# bletka_1.net
KiCad netlist of a schematic drawn in EAGLE
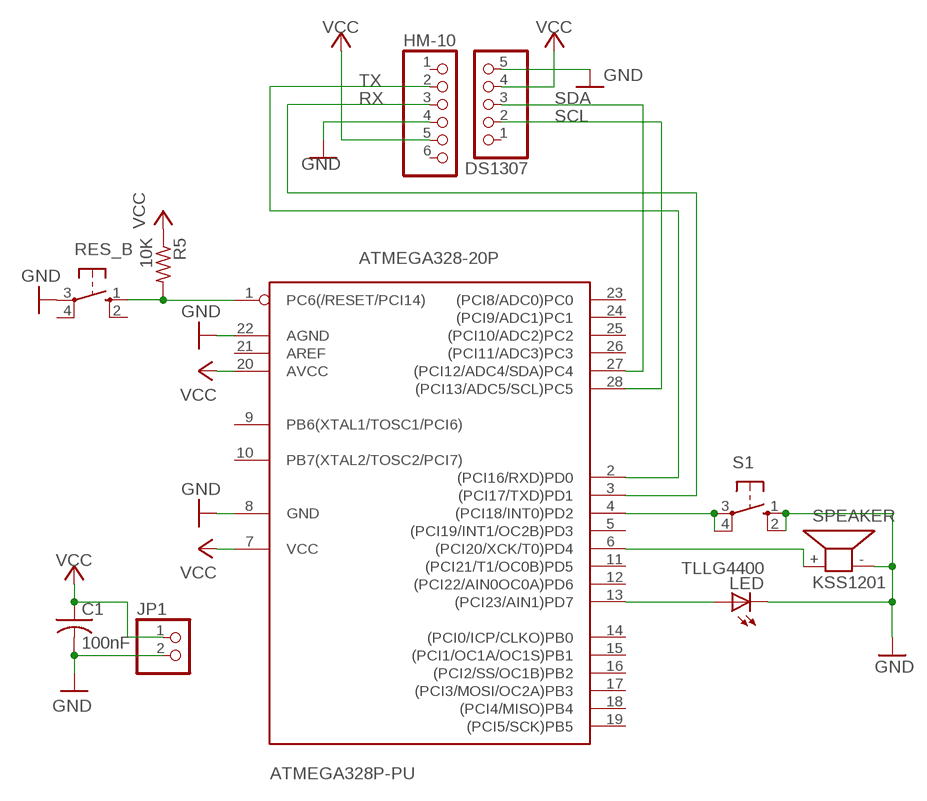
[diagram p0: schematic, sheet 1]

(export (version "E")
  (design (tool "Eeschema 10.0.6"))
  (components
    (comp (ref "ATMEGA328P-PU")
      (value "ATMEGA328-20P")
      (footprint "eagle-import:DIL28-3")
      (libsource (lib "eagle-import") (part "ATMEGA328P-20"))
    )
    (comp (ref "C1")
      (value "100nF")
      (footprint "eagle-import:C050-024X044")
      (libsource (lib "eagle-import") (part "C-US050-024X044"))
    )
    (comp (ref "DS1307")
      (value "PINHD-1X5")
      (footprint "eagle-import:1X05")
      (libsource (lib "eagle-import") (part "PINHD-1X5"))
    )
    (comp (ref "HM-10")
      (value "PINHD-1X6")
      (footprint "eagle-import:1X06")
      (libsource (lib "eagle-import") (part "PINHD-1X6"))
    )
    (comp (ref "JP1")
      (value "PINHD-1X2")
      (footprint "eagle-import:1X02")
      (libsource (lib "eagle-import") (part "PINHD-1X2"))
    )
    (comp (ref "LED")
      (value "TLLG4400")
      (footprint "eagle-import:LED3MM")
      (fields (field (name "MF") "VISHAY SEMICONDUCTOR"))
      (libsource (lib "eagle-import") (part "TLLG4400"))
    )
    (comp (ref "R5")
      (value "10K")
      (footprint "eagle-import:0207_10")
      (libsource (lib "eagle-import") (part "R-US_0207/10"))
    )
    (comp (ref "RES_B")
      (value "10-XX")
      (footprint "eagle-import:B3F-10XX")
      (fields (field (name "MPN") "B3F-1000"))
      (libsource (lib "eagle-import") (part "10-XX"))
    )
    (comp (ref "S1")
      (value "10-XX")
      (footprint "eagle-import:B3F-10XX")
      (fields (field (name "MPN") "B3F-1000"))
      (libsource (lib "eagle-import") (part "10-XX"))
    )
    (comp (ref "SPEAKER")
      (value "KSS1201")
      (footprint "eagle-import:KSS1201")
      (libsource (lib "eagle-import") (part "KSS1201"))
    )
  )
  (nets
    (net (code "1") (name "/RX") (class "Default")
      (node (ref "ATMEGA328P-PU") (pin "3") (pinfunction "(PCI17/TXD)PD1_3") (pintype "bidirectional"))
      (node (ref "HM-10") (pin "3") (pinfunction "3_3") (pintype "passive"))
    )
    (net (code "2") (name "/SCL") (class "Default")
      (node (ref "ATMEGA328P-PU") (pin "28") (pinfunction "(PCI13/ADC5/SCL)PC5_28") (pintype "bidirectional"))
      (node (ref "DS1307") (pin "2") (pinfunction "2_2") (pintype "passive"))
    )
    (net (code "3") (name "/SDA") (class "Default")
      (node (ref "ATMEGA328P-PU") (pin "27") (pinfunction "(PCI12/ADC4/SDA)PC4_27") (pintype "bidirectional"))
      (node (ref "DS1307") (pin "3") (pinfunction "3_3") (pintype "passive"))
    )
    (net (code "4") (name "/TX") (class "Default")
      (node (ref "ATMEGA328P-PU") (pin "2") (pinfunction "(PCI16/RXD)PD0_2") (pintype "bidirectional"))
      (node (ref "HM-10") (pin "2") (pinfunction "2_2") (pintype "passive"))
    )
    (net (code "5") (name "GND") (class "Default")
      (node (ref "ATMEGA328P-PU") (pin "22") (pinfunction "AGND_22") (pintype "bidirectional"))
      (node (ref "ATMEGA328P-PU") (pin "8") (pinfunction "GND_8") (pintype "bidirectional"))
      (node (ref "C1") (pin "2") (pinfunction "2_2") (pintype "passive"))
      (node (ref "DS1307") (pin "5") (pinfunction "5_5") (pintype "passive"))
      (node (ref "HM-10") (pin "4") (pinfunction "4_4") (pintype "passive"))
      (node (ref "JP1") (pin "2") (pinfunction "2_2") (pintype "passive"))
      (node (ref "LED") (pin "K") (pinfunction "C_K") (pintype "passive"))
      (node (ref "RES_B") (pin "3") (pinfunction "P_3") (pintype "passive"))
      (node (ref "S1") (pin "1") (pinfunction "S_1") (pintype "passive"))
      (node (ref "S1") (pin "2") (pinfunction "S1_2") (pintype "passive"))
      (node (ref "SPEAKER") (pin "-") (pinfunction "2_-") (pintype "passive"))
    )
    (net (code "6") (name "Net-(ATMEGA328P-PU-(PCI18{slash}INT0)PD2)") (class "Default")
      (node (ref "ATMEGA328P-PU") (pin "4") (pinfunction "(PCI18/INT0)PD2_4") (pintype "bidirectional"))
      (node (ref "S1") (pin "3") (pinfunction "P_3") (pintype "passive"))
      (node (ref "S1") (pin "4") (pinfunction "P1_4") (pintype "passive"))
    )
    (net (code "7") (name "Net-(ATMEGA328P-PU-(PCI20{slash}XCK{slash}T0)PD4)") (class "Default")
      (node (ref "ATMEGA328P-PU") (pin "6") (pinfunction "(PCI20/XCK/T0)PD4_6") (pintype "bidirectional"))
      (node (ref "SPEAKER") (pin "+") (pinfunction "1_+") (pintype "passive"))
    )
    (net (code "8") (name "Net-(ATMEGA328P-PU-(PCI23{slash}AIN1)PD7)") (class "Default")
      (node (ref "ATMEGA328P-PU") (pin "13") (pinfunction "(PCI23/AIN1)PD7_13") (pintype "bidirectional"))
      (node (ref "LED") (pin "A") (pinfunction "A_A") (pintype "passive"))
    )
    (net (code "9") (name "Net-(ATMEGA328P-PU-PC6({slash}RESET{slash}PCI14))") (class "Default")
      (node (ref "ATMEGA328P-PU") (pin "1") (pinfunction "PC6(/RESET/PCI14)_1") (pintype "bidirectional"))
      (node (ref "R5") (pin "2") (pinfunction "2_2") (pintype "passive"))
      (node (ref "RES_B") (pin "1") (pinfunction "S_1") (pintype "passive"))
    )
    (net (code "10") (name "VCC") (class "Default")
      (node (ref "ATMEGA328P-PU") (pin "20") (pinfunction "AVCC_20") (pintype "bidirectional"))
      (node (ref "ATMEGA328P-PU") (pin "7") (pinfunction "VCC_7") (pintype "bidirectional"))
      (node (ref "C1") (pin "1") (pinfunction "1_1") (pintype "passive"))
      (node (ref "DS1307") (pin "4") (pinfunction "4_4") (pintype "passive"))
      (node (ref "HM-10") (pin "5") (pinfunction "5_5") (pintype "passive"))
      (node (ref "JP1") (pin "1") (pinfunction "1_1") (pintype "passive"))
      (node (ref "R5") (pin "1") (pinfunction "1_1") (pintype "passive"))
    )
    (net (code "11") (name "unconnected-(ATMEGA328P-PU-(PCI0{slash}ICP{slash}CLKO)PB0-Pad14)") (class "Default")
      (node (ref "ATMEGA328P-PU") (pin "14") (pinfunction "(PCI0/ICP/CLKO)PB0_14") (pintype "bidirectional"))
    )
    (net (code "12") (name "unconnected-(ATMEGA328P-PU-(PCI1{slash}OC1A{slash}OC1S)PB1-Pad15)") (class "Default")
      (node (ref "ATMEGA328P-PU") (pin "15") (pinfunction "(PCI1/OC1A/OC1S)PB1_15") (pintype "bidirectional"))
    )
    (net (code "13") (name "unconnected-(ATMEGA328P-PU-(PCI2{slash}SS{slash}OC1B)PB2-Pad16)") (class "Default")
      (node (ref "ATMEGA328P-PU") (pin "16") (pinfunction "(PCI2/SS/OC1B)PB2_16") (pintype "bidirectional"))
    )
    (net (code "14") (name "unconnected-(ATMEGA328P-PU-(PCI3{slash}MOSI{slash}OC2A)PB3-Pad17)") (class "Default")
      (node (ref "ATMEGA328P-PU") (pin "17") (pinfunction "(PCI3/MOSI/OC2A)PB3_17") (pintype "bidirectional"))
    )
    (net (code "15") (name "unconnected-(ATMEGA328P-PU-(PCI4{slash}MISO)PB4-Pad18)") (class "Default")
      (node (ref "ATMEGA328P-PU") (pin "18") (pinfunction "(PCI4/MISO)PB4_18") (pintype "bidirectional"))
    )
    (net (code "16") (name "unconnected-(ATMEGA328P-PU-(PCI5{slash}SCK)PB5-Pad19)") (class "Default")
      (node (ref "ATMEGA328P-PU") (pin "19") (pinfunction "(PCI5/SCK)PB5_19") (pintype "bidirectional"))
    )
    (net (code "17") (name "unconnected-(ATMEGA328P-PU-(PCI8{slash}ADC0)PC0-Pad23)") (class "Default")
      (node (ref "ATMEGA328P-PU") (pin "23") (pinfunction "(PCI8/ADC0)PC0_23") (pintype "bidirectional"))
    )
    (net (code "18") (name "unconnected-(ATMEGA328P-PU-(PCI9{slash}ADC1)PC1-Pad24)") (class "Default")
      (node (ref "ATMEGA328P-PU") (pin "24") (pinfunction "(PCI9/ADC1)PC1_24") (pintype "bidirectional"))
    )
    (net (code "19") (name "unconnected-(ATMEGA328P-PU-(PCI10{slash}ADC2)PC2-Pad25)") (class "Default")
      (node (ref "ATMEGA328P-PU") (pin "25") (pinfunction "(PCI10/ADC2)PC2_25") (pintype "bidirectional"))
    )
    (net (code "20") (name "unconnected-(ATMEGA328P-PU-(PCI11{slash}ADC3)PC3-Pad26)") (class "Default")
      (node (ref "ATMEGA328P-PU") (pin "26") (pinfunction "(PCI11/ADC3)PC3_26") (pintype "bidirectional"))
    )
    (net (code "21") (name "unconnected-(ATMEGA328P-PU-(PCI19{slash}INT1{slash}OC2B)PD3-Pad5)") (class "Default")
      (node (ref "ATMEGA328P-PU") (pin "5") (pinfunction "(PCI19/INT1/OC2B)PD3_5") (pintype "bidirectional"))
    )
    (net (code "22") (name "unconnected-(ATMEGA328P-PU-(PCI21{slash}T1{slash}OC0B)PD5-Pad11)") (class "Default")
      (node (ref "ATMEGA328P-PU") (pin "11") (pinfunction "(PCI21/T1/OC0B)PD5_11") (pintype "bidirectional"))
    )
    (net (code "23") (name "unconnected-(ATMEGA328P-PU-(PCI22{slash}AIN0OC0A)PD6-Pad12)") (class "Default")
      (node (ref "ATMEGA328P-PU") (pin "12") (pinfunction "(PCI22/AIN0OC0A)PD6_12") (pintype "bidirectional"))
    )
    (net (code "24") (name "unconnected-(ATMEGA328P-PU-AREF-Pad21)") (class "Default")
      (node (ref "ATMEGA328P-PU") (pin "21") (pinfunction "AREF_21") (pintype "bidirectional"))
    )
    (net (code "25") (name "unconnected-(ATMEGA328P-PU-PB6(XTAL1{slash}TOSC1{slash}PCI6)-Pad9)") (class "Default")
      (node (ref "ATMEGA328P-PU") (pin "9") (pinfunction "PB6(XTAL1/TOSC1/PCI6)_9") (pintype "bidirectional"))
    )
    (net (code "26") (name "unconnected-(ATMEGA328P-PU-PB7(XTAL2{slash}TOSC2{slash}PCI7)-Pad10)") (class "Default")
      (node (ref "ATMEGA328P-PU") (pin "10") (pinfunction "PB7(XTAL2/TOSC2/PCI7)_10") (pintype "bidirectional"))
    )
    (net (code "27") (name "unconnected-(DS1307-Pad1)") (class "Default")
      (node (ref "DS1307") (pin "1") (pinfunction "1_1") (pintype "passive"))
    )
    (net (code "28") (name "unconnected-(HM-10-Pad1)") (class "Default")
      (node (ref "HM-10") (pin "1") (pinfunction "1_1") (pintype "passive"))
    )
    (net (code "29") (name "unconnected-(HM-10-Pad6)") (class "Default")
      (node (ref "HM-10") (pin "6") (pinfunction "6_6") (pintype "passive"))
    )
    (net (code "30") (name "unconnected-(RES_B-P1-Pad4)") (class "Default")
      (node (ref "RES_B") (pin "4") (pinfunction "P1_4") (pintype "passive"))
    )
    (net (code "31") (name "unconnected-(RES_B-S1-Pad2)") (class "Default")
      (node (ref "RES_B") (pin "2") (pinfunction "S1_2") (pintype "passive"))
    )
  )
)
